# v6_io_23_24_25_26.net
KiCad netlist of a schematic drawn in Altium Designer
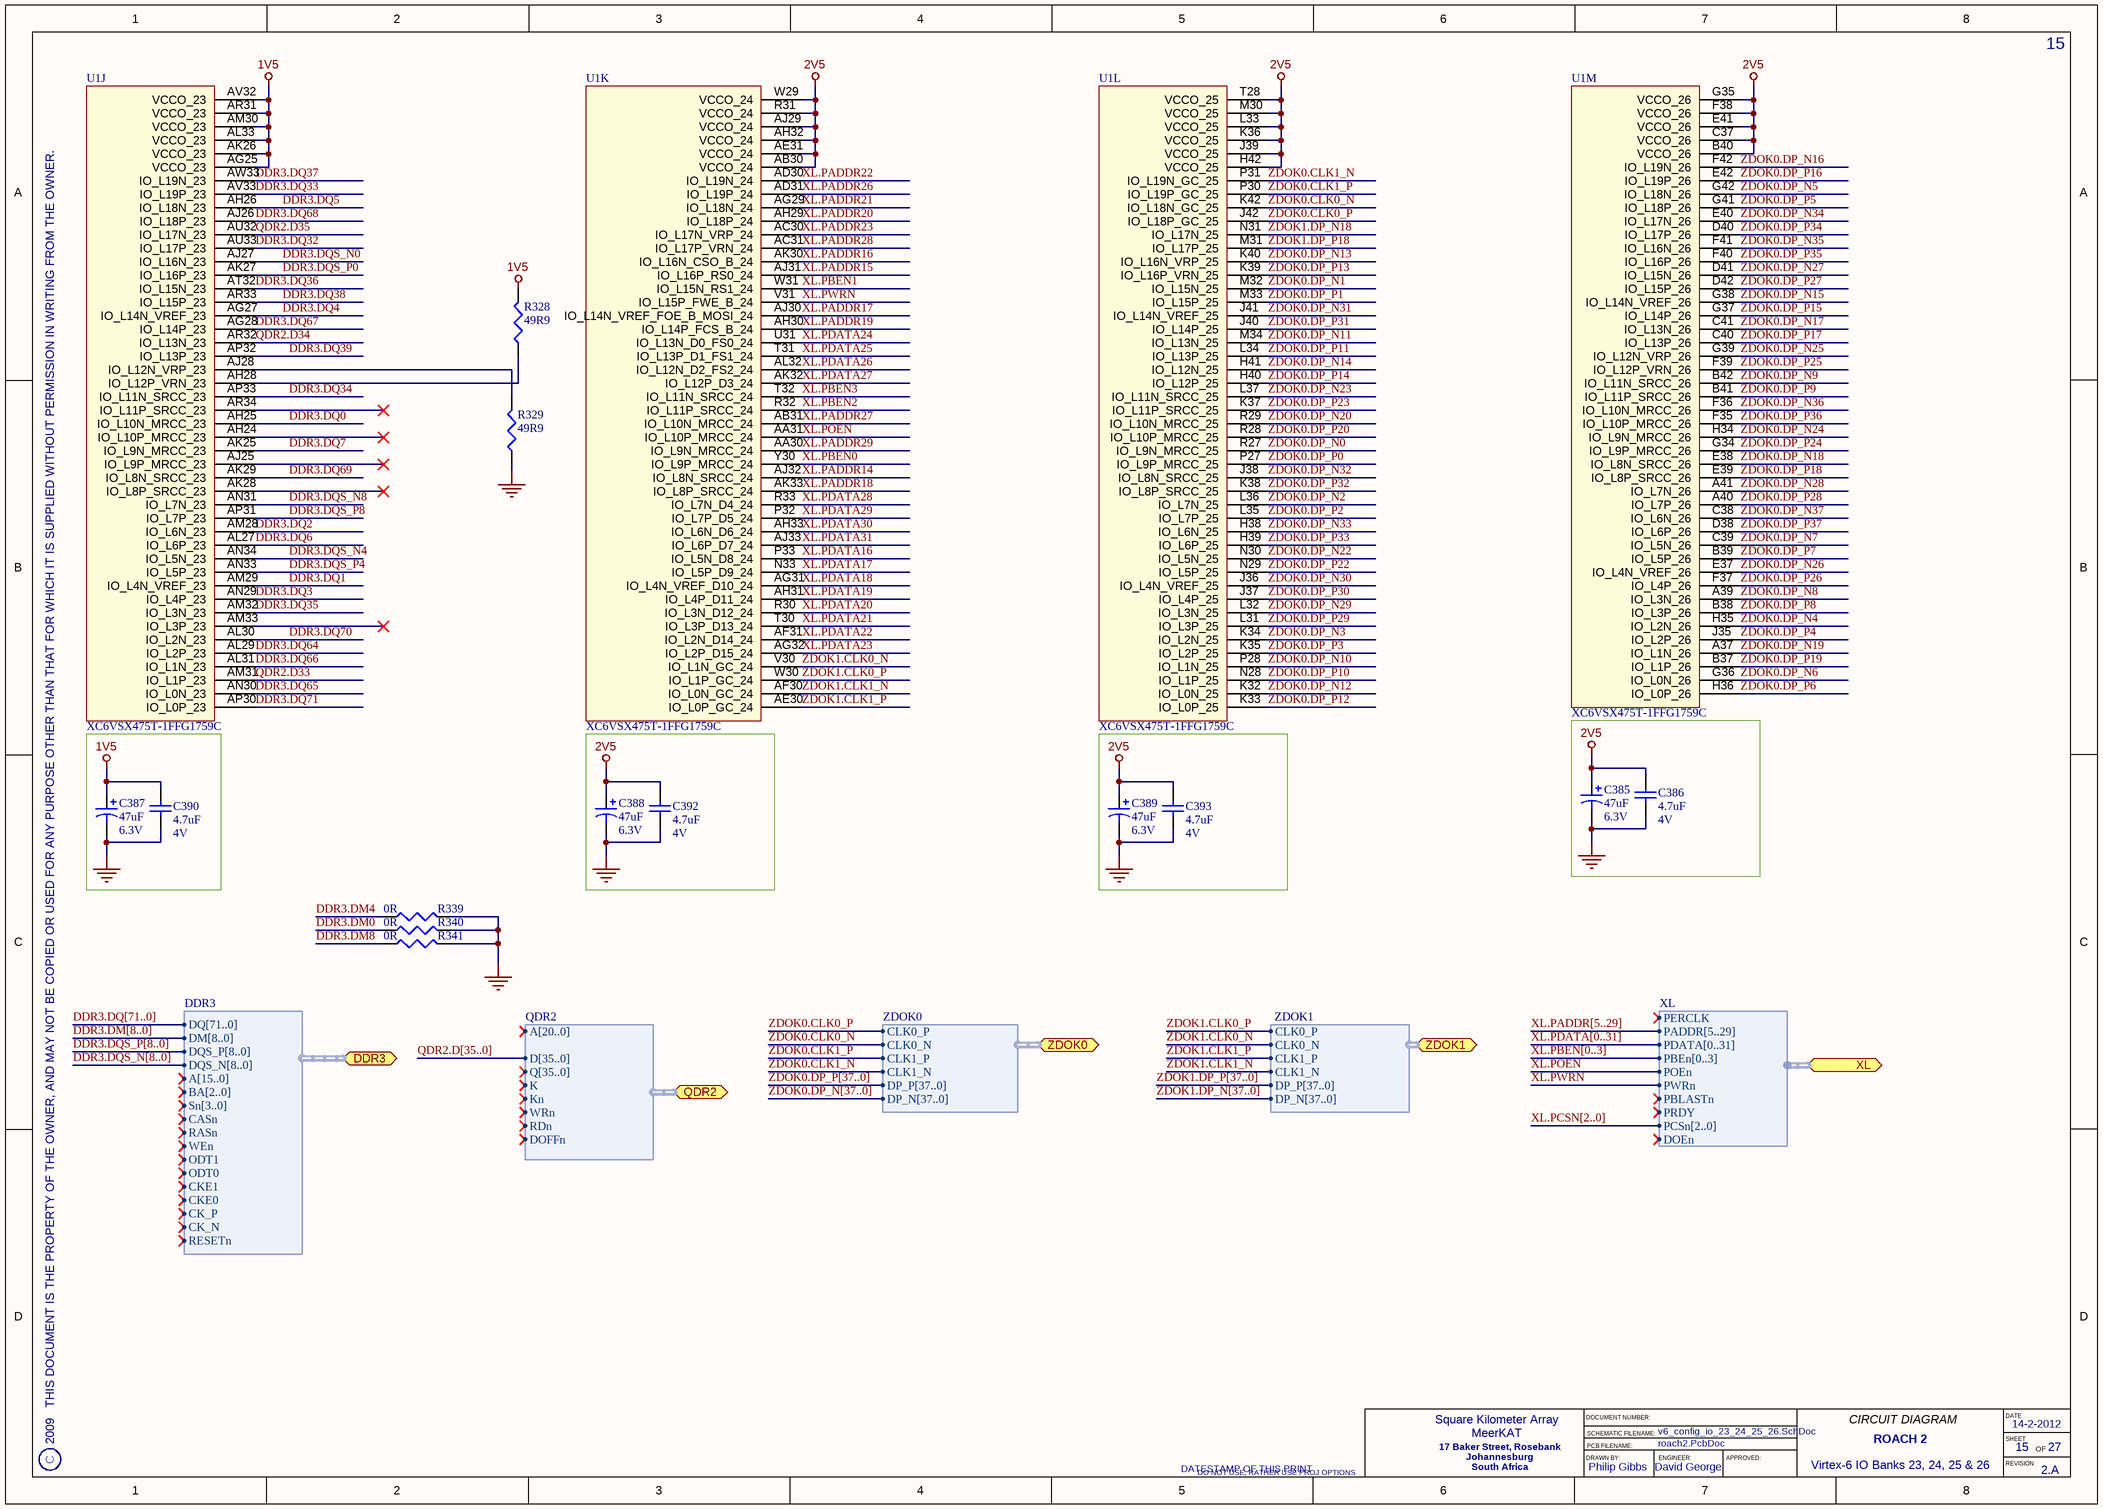
[diagram p0: v6_io_23_24_25_26.SchDoc]

(export (version "E")
  (design (tool "Eeschema 10.0.6"))
  (components
    (comp (ref "C385")
      (value "47uF")
      (footprint "CAPMP3528X120L")
      (description "47uF, Conductive Polymer Chip Capacitor")
      (fields
        (field (name "RATING") "6.3V")
        (field (name "MANUFACTURER") "KEMET")
        (field (name "PARTNUM") "T520T476M006ATE070")
      )
      (libsource (lib "altium_db") (part "CapPol"))
    )
    (comp (ref "C386")
      (value "4.7uF")
      (footprint "CAPC1005X60L")
      (description "4.7uF, Ceramic Capacitor")
      (fields
        (field (name "RATING") "4V")
        (field (name "MANUFACTURER") "MURATA")
        (field (name "PARTNUM") "AMK105BJ475MV-F")
      )
      (libsource (lib "altium_db") (part "CapStd"))
    )
    (comp (ref "C387")
      (value "47uF")
      (footprint "CAPMP3528X120L")
      (description "47uF, Conductive Polymer Chip Capacitor")
      (fields
        (field (name "RATING") "6.3V")
        (field (name "MANUFACTURER") "KEMET")
        (field (name "PARTNUM") "T520T476M006ATE070")
      )
      (libsource (lib "altium_db") (part "CapPol"))
    )
    (comp (ref "C388")
      (value "47uF")
      (footprint "CAPMP3528X120L")
      (description "47uF, Conductive Polymer Chip Capacitor")
      (fields
        (field (name "RATING") "6.3V")
        (field (name "MANUFACTURER") "KEMET")
        (field (name "PARTNUM") "T520T476M006ATE070")
      )
      (libsource (lib "altium_db") (part "CapPol"))
    )
    (comp (ref "C389")
      (value "47uF")
      (footprint "CAPMP3528X120L")
      (description "47uF, Conductive Polymer Chip Capacitor")
      (fields
        (field (name "RATING") "6.3V")
        (field (name "MANUFACTURER") "KEMET")
        (field (name "PARTNUM") "T520T476M006ATE070")
      )
      (libsource (lib "altium_db") (part "CapPol"))
    )
    (comp (ref "C390")
      (value "4.7uF")
      (footprint "CAPC1005X60L")
      (description "4.7uF, Ceramic Capacitor")
      (fields
        (field (name "RATING") "4V")
        (field (name "MANUFACTURER") "MURATA")
        (field (name "PARTNUM") "AMK105BJ475MV-F")
      )
      (libsource (lib "altium_db") (part "CapStd"))
    )
    (comp (ref "C392")
      (value "4.7uF")
      (footprint "CAPC1005X60L")
      (description "4.7uF, Ceramic Capacitor")
      (fields
        (field (name "RATING") "4V")
        (field (name "MANUFACTURER") "MURATA")
        (field (name "PARTNUM") "AMK105BJ475MV-F")
      )
      (libsource (lib "altium_db") (part "CapStd"))
    )
    (comp (ref "C393")
      (value "4.7uF")
      (footprint "CAPC1005X60L")
      (description "4.7uF, Ceramic Capacitor")
      (fields
        (field (name "RATING") "4V")
        (field (name "MANUFACTURER") "MURATA")
        (field (name "PARTNUM") "AMK105BJ475MV-F")
      )
      (libsource (lib "altium_db") (part "CapStd"))
    )
    (comp (ref "R328")
      (value "49R9")
      (footprint "RESC1005X40L")
      (description "49R9, 1.1mm x 0.5mm, Thick Film Resistor")
      (fields (field (name "MANUFACTURER") "ROYALOHM") (field (name "PARTNUM") "0402WGF499JT1E"))
      (libsource (lib "altium_db") (part "ResStd"))
    )
    (comp (ref "R329")
      (value "49R9")
      (footprint "RESC1005X40L")
      (description "49R9, 1.1mm x 0.5mm, Thick Film Resistor")
      (fields (field (name "MANUFACTURER") "ROYALOHM") (field (name "PARTNUM") "0402WGF499JT1E"))
      (libsource (lib "altium_db") (part "ResStd"))
    )
    (comp (ref "R339")
      (value "0R")
      (footprint "RESC1005X40L")
      (description "0R, 1.1mm x 0.5mm, Thick Film Resistor")
      (fields (field (name "MANUFACTURER") "ROYALOHM") (field (name "PARTNUM") "0402WG00000T1E"))
      (libsource (lib "altium_db") (part "ResStd"))
    )
    (comp (ref "R340")
      (value "0R")
      (footprint "RESC1005X40L")
      (description "0R, 1.1mm x 0.5mm, Thick Film Resistor")
      (fields (field (name "MANUFACTURER") "ROYALOHM") (field (name "PARTNUM") "0402WG00000T1E"))
      (libsource (lib "altium_db") (part "ResStd"))
    )
    (comp (ref "R341")
      (value "0R")
      (footprint "RESC1005X40L")
      (description "0R, 1.1mm x 0.5mm, Thick Film Resistor")
      (fields (field (name "MANUFACTURER") "ROYALOHM") (field (name "PARTNUM") "0402WG00000T1E"))
      (libsource (lib "altium_db") (part "ResStd"))
    )
    (comp (ref "U1")
      (value "XC6VSX475T-1FFG1759C")
      (footprint "FFG1759")
      (description "Virtex-6 475SXT 1760-pin FPGA")
      (fields (field (name "MANUFACTURER") "Xilinx"))
      (libsource (lib "altium_db") (part "XC6VSX475T-1FFG1759C"))
    )
  )
  (nets
    (net (code "171") (name "/DDR3.DM0") (class "Default")
      (node (ref "R340") (pin "1") (pinfunction "1_1") (pintype "passive"))
    )
    (net (code "172") (name "/DDR3.DM4") (class "Default")
      (node (ref "R339") (pin "1") (pinfunction "1_1") (pintype "passive"))
    )
    (net (code "173") (name "/DDR3.DM8") (class "Default")
      (node (ref "R341") (pin "1") (pinfunction "1_1") (pintype "passive"))
    )
    (net (code "175") (name "/DDR3.DQ0") (class "Default")
      (node (ref "U1") (pin "AH25") (pinfunction "IO_L10N_MRCC_23_AH25") (pintype "passive"))
    )
    (net (code "176") (name "/DDR3.DQ1") (class "Default")
      (node (ref "U1") (pin "AM29") (pinfunction "IO_L4N_VREF_23_AM29") (pintype "passive"))
    )
    (net (code "177") (name "/DDR3.DQ2") (class "Default")
      (node (ref "U1") (pin "AM28") (pinfunction "IO_L6N_23_AM28") (pintype "passive"))
    )
    (net (code "178") (name "/DDR3.DQ3") (class "Default")
      (node (ref "U1") (pin "AN29") (pinfunction "IO_L4P_23_AN29") (pintype "passive"))
    )
    (net (code "179") (name "/DDR3.DQ4") (class "Default")
      (node (ref "U1") (pin "AG27") (pinfunction "IO_L14N_VREF_23_AG27") (pintype "passive"))
    )
    (net (code "180") (name "/DDR3.DQ5") (class "Default")
      (node (ref "U1") (pin "AH26") (pinfunction "IO_L18N_23_AH26") (pintype "passive"))
    )
    (net (code "181") (name "/DDR3.DQ6") (class "Default")
      (node (ref "U1") (pin "AL27") (pinfunction "IO_L6P_23_AL27") (pintype "passive"))
    )
    (net (code "182") (name "/DDR3.DQ7") (class "Default")
      (node (ref "U1") (pin "AK25") (pinfunction "IO_L9N_MRCC_23_AK25") (pintype "passive"))
    )
    (net (code "183") (name "/DDR3.DQ32") (class "Default")
      (node (ref "U1") (pin "AU33") (pinfunction "IO_L17P_23_AU33") (pintype "passive"))
    )
    (net (code "184") (name "/DDR3.DQ33") (class "Default")
      (node (ref "U1") (pin "AV33") (pinfunction "IO_L19P_23_AV33") (pintype "passive"))
    )
    (net (code "185") (name "/DDR3.DQ34") (class "Default")
      (node (ref "U1") (pin "AP33") (pinfunction "IO_L11N_SRCC_23_AP33") (pintype "passive"))
    )
    (net (code "186") (name "/DDR3.DQ35") (class "Default")
      (node (ref "U1") (pin "AM32") (pinfunction "IO_L3N_23_AM32") (pintype "passive"))
    )
    (net (code "187") (name "/DDR3.DQ36") (class "Default")
      (node (ref "U1") (pin "AT32") (pinfunction "IO_L15N_23_AT32") (pintype "passive"))
    )
    (net (code "188") (name "/DDR3.DQ37") (class "Default")
      (node (ref "U1") (pin "AW33") (pinfunction "IO_L19N_23_AW33") (pintype "passive"))
    )
    (net (code "189") (name "/DDR3.DQ38") (class "Default")
      (node (ref "U1") (pin "AR33") (pinfunction "IO_L15P_23_AR33") (pintype "passive"))
    )
    (net (code "190") (name "/DDR3.DQ39") (class "Default")
      (node (ref "U1") (pin "AP32") (pinfunction "IO_L13P_23_AP32") (pintype "passive"))
    )
    (net (code "191") (name "/DDR3.DQ64") (class "Default")
      (node (ref "U1") (pin "AL29") (pinfunction "IO_L2P_23_AL29") (pintype "passive"))
    )
    (net (code "192") (name "/DDR3.DQ65") (class "Default")
      (node (ref "U1") (pin "AN30") (pinfunction "IO_L0N_23_AN30") (pintype "passive"))
    )
    (net (code "193") (name "/DDR3.DQ66") (class "Default")
      (node (ref "U1") (pin "AL31") (pinfunction "IO_L1N_23_AL31") (pintype "passive"))
    )
    (net (code "194") (name "/DDR3.DQ67") (class "Default")
      (node (ref "U1") (pin "AG28") (pinfunction "IO_L14P_23_AG28") (pintype "passive"))
    )
    (net (code "195") (name "/DDR3.DQ68") (class "Default")
      (node (ref "U1") (pin "AJ26") (pinfunction "IO_L18P_23_AJ26") (pintype "passive"))
    )
    (net (code "196") (name "/DDR3.DQ69") (class "Default")
      (node (ref "U1") (pin "AK29") (pinfunction "IO_L8N_SRCC_23_AK29") (pintype "passive"))
    )
    (net (code "197") (name "/DDR3.DQ70") (class "Default")
      (node (ref "U1") (pin "AL30") (pinfunction "IO_L2N_23_AL30") (pintype "passive"))
    )
    (net (code "198") (name "/DDR3.DQ71") (class "Default")
      (node (ref "U1") (pin "AP30") (pinfunction "IO_L0P_23_AP30") (pintype "passive"))
    )
    (net (code "199") (name "/DDR3.DQS_N0") (class "Default")
      (node (ref "U1") (pin "AJ27") (pinfunction "IO_L16N_23_AJ27") (pintype "passive"))
    )
    (net (code "200") (name "/DDR3.DQS_N4") (class "Default")
      (node (ref "U1") (pin "AN34") (pinfunction "IO_L5N_23_AN34") (pintype "passive"))
    )
    (net (code "201") (name "/DDR3.DQS_N8") (class "Default")
      (node (ref "U1") (pin "AN31") (pinfunction "IO_L7N_23_AN31") (pintype "passive"))
    )
    (net (code "203") (name "/DDR3.DQS_P0") (class "Default")
      (node (ref "U1") (pin "AK27") (pinfunction "IO_L16P_23_AK27") (pintype "passive"))
    )
    (net (code "204") (name "/DDR3.DQS_P4") (class "Default")
      (node (ref "U1") (pin "AN33") (pinfunction "IO_L5P_23_AN33") (pintype "passive"))
    )
    (net (code "205") (name "/DDR3.DQS_P8") (class "Default")
      (node (ref "U1") (pin "AP31") (pinfunction "IO_L7P_23_AP31") (pintype "passive"))
    )
    (net (code "208") (name "/QDR2.D33") (class "Default")
      (node (ref "U1") (pin "AM31") (pinfunction "IO_L1P_23_AM31") (pintype "passive"))
    )
    (net (code "209") (name "/QDR2.D34") (class "Default")
      (node (ref "U1") (pin "AR32") (pinfunction "IO_L13N_23_AR32") (pintype "passive"))
    )
    (net (code "210") (name "/QDR2.D35") (class "Default")
      (node (ref "U1") (pin "AU32") (pinfunction "IO_L17N_23_AU32") (pintype "passive"))
    )
    (net (code "212") (name "/XL.PADDR14") (class "Default")
      (node (ref "U1") (pin "AJ32") (pinfunction "IO_L8N_SRCC_24_AJ32") (pintype "passive"))
    )
    (net (code "213") (name "/XL.PADDR15") (class "Default")
      (node (ref "U1") (pin "AJ31") (pinfunction "IO_L16P_RS0_24_AJ31") (pintype "passive"))
    )
    (net (code "214") (name "/XL.PADDR16") (class "Default")
      (node (ref "U1") (pin "AK30") (pinfunction "IO_L16N_CSO_B_24_AK30") (pintype "passive"))
    )
    (net (code "215") (name "/XL.PADDR17") (class "Default")
      (node (ref "U1") (pin "AJ30") (pinfunction "IO_L14N_VREF_FOE_B_MOSI_24_AJ30") (pintype "passive"))
    )
    (net (code "216") (name "/XL.PADDR18") (class "Default")
      (node (ref "U1") (pin "AK33") (pinfunction "IO_L8P_SRCC_24_AK33") (pintype "passive"))
    )
    (net (code "217") (name "/XL.PADDR19") (class "Default")
      (node (ref "U1") (pin "AH30") (pinfunction "IO_L14P_FCS_B_24_AH30") (pintype "passive"))
    )
    (net (code "218") (name "/XL.PADDR20") (class "Default")
      (node (ref "U1") (pin "AH29") (pinfunction "IO_L18P_24_AH29") (pintype "passive"))
    )
    (net (code "219") (name "/XL.PADDR21") (class "Default")
      (node (ref "U1") (pin "AG29") (pinfunction "IO_L18N_24_AG29") (pintype "passive"))
    )
    (net (code "220") (name "/XL.PADDR22") (class "Default")
      (node (ref "U1") (pin "AD30") (pinfunction "IO_L19N_24_AD30") (pintype "passive"))
    )
    (net (code "221") (name "/XL.PADDR23") (class "Default")
      (node (ref "U1") (pin "AC30") (pinfunction "IO_L17N_VRP_24_AC30") (pintype "passive"))
    )
    (net (code "222") (name "/XL.PADDR26") (class "Default")
      (node (ref "U1") (pin "AD31") (pinfunction "IO_L19P_24_AD31") (pintype "passive"))
    )
    (net (code "223") (name "/XL.PADDR27") (class "Default")
      (node (ref "U1") (pin "AB31") (pinfunction "IO_L10N_MRCC_24_AB31") (pintype "passive"))
    )
    (net (code "224") (name "/XL.PADDR28") (class "Default")
      (node (ref "U1") (pin "AC31") (pinfunction "IO_L17P_VRN_24_AC31") (pintype "passive"))
    )
    (net (code "225") (name "/XL.PADDR29") (class "Default")
      (node (ref "U1") (pin "AA30") (pinfunction "IO_L9N_MRCC_24_AA30") (pintype "passive"))
    )
    (net (code "227") (name "/XL.PBEN0") (class "Default")
      (node (ref "U1") (pin "Y30") (pinfunction "IO_L9P_MRCC_24_Y30") (pintype "passive"))
    )
    (net (code "228") (name "/XL.PBEN1") (class "Default")
      (node (ref "U1") (pin "W31") (pinfunction "IO_L15N_RS1_24_W31") (pintype "passive"))
    )
    (net (code "229") (name "/XL.PBEN2") (class "Default")
      (node (ref "U1") (pin "R32") (pinfunction "IO_L11P_SRCC_24_R32") (pintype "passive"))
    )
    (net (code "230") (name "/XL.PBEN3") (class "Default")
      (node (ref "U1") (pin "T32") (pinfunction "IO_L11N_SRCC_24_T32") (pintype "passive"))
    )
    (net (code "232") (name "/XL.PDATA16") (class "Default")
      (node (ref "U1") (pin "P33") (pinfunction "IO_L5N_D8_24_P33") (pintype "passive"))
    )
    (net (code "233") (name "/XL.PDATA17") (class "Default")
      (node (ref "U1") (pin "N33") (pinfunction "IO_L5P_D9_24_N33") (pintype "passive"))
    )
    (net (code "234") (name "/XL.PDATA18") (class "Default")
      (node (ref "U1") (pin "AG31") (pinfunction "IO_L4N_VREF_D10_24_AG31") (pintype "passive"))
    )
    (net (code "235") (name "/XL.PDATA19") (class "Default")
      (node (ref "U1") (pin "AH31") (pinfunction "IO_L4P_D11_24_AH31") (pintype "passive"))
    )
    (net (code "236") (name "/XL.PDATA20") (class "Default")
      (node (ref "U1") (pin "R30") (pinfunction "IO_L3N_D12_24_R30") (pintype "passive"))
    )
    (net (code "237") (name "/XL.PDATA21") (class "Default")
      (node (ref "U1") (pin "T30") (pinfunction "IO_L3P_D13_24_T30") (pintype "passive"))
    )
    (net (code "238") (name "/XL.PDATA22") (class "Default")
      (node (ref "U1") (pin "AF31") (pinfunction "IO_L2N_D14_24_AF31") (pintype "passive"))
    )
    (net (code "239") (name "/XL.PDATA23") (class "Default")
      (node (ref "U1") (pin "AG32") (pinfunction "IO_L2P_D15_24_AG32") (pintype "passive"))
    )
    (net (code "240") (name "/XL.PDATA24") (class "Default")
      (node (ref "U1") (pin "U31") (pinfunction "IO_L13N_D0_FS0_24_U31") (pintype "passive"))
    )
    (net (code "241") (name "/XL.PDATA25") (class "Default")
      (node (ref "U1") (pin "T31") (pinfunction "IO_L13P_D1_FS1_24_T31") (pintype "passive"))
    )
    (net (code "242") (name "/XL.PDATA26") (class "Default")
      (node (ref "U1") (pin "AL32") (pinfunction "IO_L12N_D2_FS2_24_AL32") (pintype "passive"))
    )
    (net (code "243") (name "/XL.PDATA27") (class "Default")
      (node (ref "U1") (pin "AK32") (pinfunction "IO_L12P_D3_24_AK32") (pintype "passive"))
    )
    (net (code "244") (name "/XL.PDATA28") (class "Default")
      (node (ref "U1") (pin "R33") (pinfunction "IO_L7N_D4_24_R33") (pintype "passive"))
    )
    (net (code "245") (name "/XL.PDATA29") (class "Default")
      (node (ref "U1") (pin "P32") (pinfunction "IO_L7P_D5_24_P32") (pintype "passive"))
    )
    (net (code "246") (name "/XL.PDATA30") (class "Default")
      (node (ref "U1") (pin "AH33") (pinfunction "IO_L6N_D6_24_AH33") (pintype "passive"))
    )
    (net (code "247") (name "/XL.PDATA31") (class "Default")
      (node (ref "U1") (pin "AJ33") (pinfunction "IO_L6P_D7_24_AJ33") (pintype "passive"))
    )
    (net (code "249") (name "/XL.POEN") (class "Default")
      (node (ref "U1") (pin "AA31") (pinfunction "IO_L10P_MRCC_24_AA31") (pintype "passive"))
    )
    (net (code "250") (name "/XL.PWRN") (class "Default")
      (node (ref "U1") (pin "V31") (pinfunction "IO_L15P_FWE_B_24_V31") (pintype "passive"))
    )
    (net (code "252") (name "/ZDOK0.CLK0_N") (class "Default")
      (node (ref "U1") (pin "K42") (pinfunction "IO_L18N_GC_25_K42") (pintype "passive"))
    )
    (net (code "253") (name "/ZDOK0.CLK0_P") (class "Default")
      (node (ref "U1") (pin "J42") (pinfunction "IO_L18P_GC_25_J42") (pintype "passive"))
    )
    (net (code "254") (name "/ZDOK0.CLK1_N") (class "Default")
      (node (ref "U1") (pin "P31") (pinfunction "IO_L19N_GC_25_P31") (pintype "passive"))
    )
    (net (code "255") (name "/ZDOK0.CLK1_P") (class "Default")
      (node (ref "U1") (pin "P30") (pinfunction "IO_L19P_GC_25_P30") (pintype "passive"))
    )
    (net (code "256") (name "/ZDOK0.DP_N0") (class "Default")
      (node (ref "U1") (pin "R27") (pinfunction "IO_L9N_MRCC_25_R27") (pintype "passive"))
    )
    (net (code "257") (name "/ZDOK0.DP_N1") (class "Default")
      (node (ref "U1") (pin "M32") (pinfunction "IO_L15N_25_M32") (pintype "passive"))
    )
    (net (code "258") (name "/ZDOK0.DP_N2") (class "Default")
      (node (ref "U1") (pin "L36") (pinfunction "IO_L7N_25_L36") (pintype "passive"))
    )
    (net (code "259") (name "/ZDOK0.DP_N3") (class "Default")
      (node (ref "U1") (pin "K34") (pinfunction "IO_L2N_25_K34") (pintype "passive"))
    )
    (net (code "260") (name "/ZDOK0.DP_N4") (class "Default")
      (node (ref "U1") (pin "H35") (pinfunction "IO_L2N_26_H35") (pintype "passive"))
    )
    (net (code "261") (name "/ZDOK0.DP_N5") (class "Default")
      (node (ref "U1") (pin "G42") (pinfunction "IO_L18N_26_G42") (pintype "passive"))
    )
    (net (code "262") (name "/ZDOK0.DP_N6") (class "Default")
      (node (ref "U1") (pin "G36") (pinfunction "IO_L0N_26_G36") (pintype "passive"))
    )
    (net (code "263") (name "/ZDOK0.DP_N7") (class "Default")
      (node (ref "U1") (pin "C39") (pinfunction "IO_L5N_26_C39") (pintype "passive"))
    )
    (net (code "264") (name "/ZDOK0.DP_N8") (class "Default")
      (node (ref "U1") (pin "A39") (pinfunction "IO_L3N_26_A39") (pintype "passive"))
    )
    (net (code "265") (name "/ZDOK0.DP_N9") (class "Default")
      (node (ref "U1") (pin "B42") (pinfunction "IO_L11N_SRCC_26_B42") (pintype "passive"))
    )
    (net (code "266") (name "/ZDOK0.DP_N10") (class "Default")
      (node (ref "U1") (pin "P28") (pinfunction "IO_L1N_25_P28") (pintype "passive"))
    )
    (net (code "267") (name "/ZDOK0.DP_N11") (class "Default")
      (node (ref "U1") (pin "M34") (pinfunction "IO_L13N_25_M34") (pintype "passive"))
    )
    (net (code "268") (name "/ZDOK0.DP_N12") (class "Default")
      (node (ref "U1") (pin "K32") (pinfunction "IO_L0N_25_K32") (pintype "passive"))
    )
    (net (code "269") (name "/ZDOK0.DP_N13") (class "Default")
      (node (ref "U1") (pin "K40") (pinfunction "IO_L16N_VRP_25_K40") (pintype "passive"))
    )
    (net (code "270") (name "/ZDOK0.DP_N14") (class "Default")
      (node (ref "U1") (pin "H41") (pinfunction "IO_L12N_25_H41") (pintype "passive"))
    )
    (net (code "271") (name "/ZDOK0.DP_N15") (class "Default")
      (node (ref "U1") (pin "G38") (pinfunction "IO_L14N_VREF_26_G38") (pintype "passive"))
    )
    (net (code "272") (name "/ZDOK0.DP_N16") (class "Default")
      (node (ref "U1") (pin "F42") (pinfunction "IO_L19N_26_F42") (pintype "passive"))
    )
    (net (code "273") (name "/ZDOK0.DP_N17") (class "Default")
      (node (ref "U1") (pin "C41") (pinfunction "IO_L13N_26_C41") (pintype "passive"))
    )
    (net (code "274") (name "/ZDOK0.DP_N18") (class "Default")
      (node (ref "U1") (pin "E38") (pinfunction "IO_L8N_SRCC_26_E38") (pintype "passive"))
    )
    (net (code "275") (name "/ZDOK0.DP_N19") (class "Default")
      (node (ref "U1") (pin "A37") (pinfunction "IO_L1N_26_A37") (pintype "passive"))
    )
    (net (code "276") (name "/ZDOK0.DP_N20") (class "Default")
      (node (ref "U1") (pin "R29") (pinfunction "IO_L10N_MRCC_25_R29") (pintype "passive"))
    )
    (net (code "277") (name "/ZDOK0.DP_N22") (class "Default")
      (node (ref "U1") (pin "N30") (pinfunction "IO_L5N_25_N30") (pintype "passive"))
    )
    (net (code "278") (name "/ZDOK0.DP_N23") (class "Default")
      (node (ref "U1") (pin "L37") (pinfunction "IO_L11N_SRCC_25_L37") (pintype "passive"))
    )
    (net (code "279") (name "/ZDOK0.DP_N24") (class "Default")
      (node (ref "U1") (pin "H34") (pinfunction "IO_L9N_MRCC_26_H34") (pintype "passive"))
    )
    (net (code "280") (name "/ZDOK0.DP_N25") (class "Default")
      (node (ref "U1") (pin "G39") (pinfunction "IO_L12N_VRP_26_G39") (pintype "passive"))
    )
    (net (code "281") (name "/ZDOK0.DP_N26") (class "Default")
      (node (ref "U1") (pin "E37") (pinfunction "IO_L4N_VREF_26_E37") (pintype "passive"))
    )
    (net (code "282") (name "/ZDOK0.DP_N27") (class "Default")
      (node (ref "U1") (pin "D41") (pinfunction "IO_L15N_26_D41") (pintype "passive"))
    )
    (net (code "283") (name "/ZDOK0.DP_N28") (class "Default")
      (node (ref "U1") (pin "A41") (pinfunction "IO_L7N_26_A41") (pintype "passive"))
    )
    (net (code "284") (name "/ZDOK0.DP_N29") (class "Default")
      (node (ref "U1") (pin "L32") (pinfunction "IO_L3N_25_L32") (pintype "passive"))
    )
    (net (code "285") (name "/ZDOK0.DP_N30") (class "Default")
      (node (ref "U1") (pin "J36") (pinfunction "IO_L4N_VREF_25_J36") (pintype "passive"))
    )
    (net (code "286") (name "/ZDOK0.DP_N31") (class "Default")
      (node (ref "U1") (pin "J41") (pinfunction "IO_L14N_VREF_25_J41") (pintype "passive"))
    )
    (net (code "287") (name "/ZDOK0.DP_N32") (class "Default")
      (node (ref "U1") (pin "J38") (pinfunction "IO_L8N_SRCC_25_J38") (pintype "passive"))
    )
    (net (code "288") (name "/ZDOK0.DP_N33") (class "Default")
      (node (ref "U1") (pin "H38") (pinfunction "IO_L6N_25_H38") (pintype "passive"))
    )
    (net (code "289") (name "/ZDOK0.DP_N34") (class "Default")
      (node (ref "U1") (pin "E40") (pinfunction "IO_L17N_26_E40") (pintype "passive"))
    )
    (net (code "290") (name "/ZDOK0.DP_N35") (class "Default")
      (node (ref "U1") (pin "F41") (pinfunction "IO_L16N_26_F41") (pintype "passive"))
    )
    (net (code "291") (name "/ZDOK0.DP_N36") (class "Default")
      (node (ref "U1") (pin "F36") (pinfunction "IO_L10N_MRCC_26_F36") (pintype "passive"))
    )
    (net (code "292") (name "/ZDOK0.DP_N37") (class "Default")
      (node (ref "U1") (pin "C38") (pinfunction "IO_L6N_26_C38") (pintype "passive"))
    )
    (net (code "294") (name "/ZDOK0.DP_P0") (class "Default")
      (node (ref "U1") (pin "P27") (pinfunction "IO_L9P_MRCC_25_P27") (pintype "passive"))
    )
    (net (code "295") (name "/ZDOK0.DP_P1") (class "Default")
      (node (ref "U1") (pin "M33") (pinfunction "IO_L15P_25_M33") (pintype "passive"))
    )
    (net (code "296") (name "/ZDOK0.DP_P2") (class "Default")
      (node (ref "U1") (pin "L35") (pinfunction "IO_L7P_25_L35") (pintype "passive"))
    )
    (net (code "297") (name "/ZDOK0.DP_P3") (class "Default")
      (node (ref "U1") (pin "K35") (pinfunction "IO_L2P_25_K35") (pintype "passive"))
    )
    (net (code "298") (name "/ZDOK0.DP_P4") (class "Default")
      (node (ref "U1") (pin "J35") (pinfunction "IO_L2P_26_J35") (pintype "passive"))
    )
    (net (code "299") (name "/ZDOK0.DP_P5") (class "Default")
      (node (ref "U1") (pin "G41") (pinfunction "IO_L18P_26_G41") (pintype "passive"))
    )
    (net (code "300") (name "/ZDOK0.DP_P6") (class "Default")
      (node (ref "U1") (pin "H36") (pinfunction "IO_L0P_26_H36") (pintype "passive"))
    )
    (net (code "301") (name "/ZDOK0.DP_P7") (class "Default")
      (node (ref "U1") (pin "B39") (pinfunction "IO_L5P_26_B39") (pintype "passive"))
    )
    (net (code "302") (name "/ZDOK0.DP_P8") (class "Default")
      (node (ref "U1") (pin "B38") (pinfunction "IO_L3P_26_B38") (pintype "passive"))
    )
    (net (code "303") (name "/ZDOK0.DP_P9") (class "Default")
      (node (ref "U1") (pin "B41") (pinfunction "IO_L11P_SRCC_26_B41") (pintype "passive"))
    )
    (net (code "304") (name "/ZDOK0.DP_P10") (class "Default")
      (node (ref "U1") (pin "N28") (pinfunction "IO_L1P_25_N28") (pintype "passive"))
    )
    (net (code "305") (name "/ZDOK0.DP_P11") (class "Default")
      (node (ref "U1") (pin "L34") (pinfunction "IO_L13P_25_L34") (pintype "passive"))
    )
    (net (code "306") (name "/ZDOK0.DP_P12") (class "Default")
      (node (ref "U1") (pin "K33") (pinfunction "IO_L0P_25_K33") (pintype "passive"))
    )
    (net (code "307") (name "/ZDOK0.DP_P13") (class "Default")
      (node (ref "U1") (pin "K39") (pinfunction "IO_L16P_VRN_25_K39") (pintype "passive"))
    )
    (net (code "308") (name "/ZDOK0.DP_P14") (class "Default")
      (node (ref "U1") (pin "H40") (pinfunction "IO_L12P_25_H40") (pintype "passive"))
    )
    (net (code "309") (name "/ZDOK0.DP_P15") (class "Default")
      (node (ref "U1") (pin "G37") (pinfunction "IO_L14P_26_G37") (pintype "passive"))
    )
    (net (code "310") (name "/ZDOK0.DP_P16") (class "Default")
      (node (ref "U1") (pin "E42") (pinfunction "IO_L19P_26_E42") (pintype "passive"))
    )
    (net (code "311") (name "/ZDOK0.DP_P17") (class "Default")
      (node (ref "U1") (pin "C40") (pinfunction "IO_L13P_26_C40") (pintype "passive"))
    )
    (net (code "312") (name "/ZDOK0.DP_P18") (class "Default")
      (node (ref "U1") (pin "E39") (pinfunction "IO_L8P_SRCC_26_E39") (pintype "passive"))
    )
    (net (code "313") (name "/ZDOK0.DP_P19") (class "Default")
      (node (ref "U1") (pin "B37") (pinfunction "IO_L1P_26_B37") (pintype "passive"))
    )
    (net (code "314") (name "/ZDOK0.DP_P20") (class "Default")
      (node (ref "U1") (pin "R28") (pinfunction "IO_L10P_MRCC_25_R28") (pintype "passive"))
    )
    (net (code "315") (name "/ZDOK0.DP_P22") (class "Default")
      (node (ref "U1") (pin "N29") (pinfunction "IO_L5P_25_N29") (pintype "passive"))
    )
    (net (code "316") (name "/ZDOK0.DP_P23") (class "Default")
      (node (ref "U1") (pin "K37") (pinfunction "IO_L11P_SRCC_25_K37") (pintype "passive"))
    )
    (net (code "317") (name "/ZDOK0.DP_P24") (class "Default")
      (node (ref "U1") (pin "G34") (pinfunction "IO_L9P_MRCC_26_G34") (pintype "passive"))
    )
    (net (code "318") (name "/ZDOK0.DP_P25") (class "Default")
      (node (ref "U1") (pin "F39") (pinfunction "IO_L12P_VRN_26_F39") (pintype "passive"))
    )
    (net (code "319") (name "/ZDOK0.DP_P26") (class "Default")
      (node (ref "U1") (pin "F37") (pinfunction "IO_L4P_26_F37") (pintype "passive"))
    )
    (net (code "320") (name "/ZDOK0.DP_P27") (class "Default")
      (node (ref "U1") (pin "D42") (pinfunction "IO_L15P_26_D42") (pintype "passive"))
    )
    (net (code "321") (name "/ZDOK0.DP_P28") (class "Default")
      (node (ref "U1") (pin "A40") (pinfunction "IO_L7P_26_A40") (pintype "passive"))
    )
    (net (code "322") (name "/ZDOK0.DP_P29") (class "Default")
      (node (ref "U1") (pin "L31") (pinfunction "IO_L3P_25_L31") (pintype "passive"))
    )
    (net (code "323") (name "/ZDOK0.DP_P30") (class "Default")
      (node (ref "U1") (pin "J37") (pinfunction "IO_L4P_25_J37") (pintype "passive"))
    )
    (net (code "324") (name "/ZDOK0.DP_P31") (class "Default")
      (node (ref "U1") (pin "J40") (pinfunction "IO_L14P_25_J40") (pintype "passive"))
    )
    (net (code "325") (name "/ZDOK0.DP_P32") (class "Default")
      (node (ref "U1") (pin "K38") (pinfunction "IO_L8P_SRCC_25_K38") (pintype "passive"))
    )
    (net (code "326") (name "/ZDOK0.DP_P33") (class "Default")
      (node (ref "U1") (pin "H39") (pinfunction "IO_L6P_25_H39") (pintype "passive"))
    )
    (net (code "327") (name "/ZDOK0.DP_P34") (class "Default")
      (node (ref "U1") (pin "D40") (pinfunction "IO_L17P_26_D40") (pintype "passive"))
    )
    (net (code "328") (name "/ZDOK0.DP_P35") (class "Default")
      (node (ref "U1") (pin "F40") (pinfunction "IO_L16P_26_F40") (pintype "passive"))
    )
    (net (code "329") (name "/ZDOK0.DP_P36") (class "Default")
      (node (ref "U1") (pin "F35") (pinfunction "IO_L10P_MRCC_26_F35") (pintype "passive"))
    )
    (net (code "330") (name "/ZDOK0.DP_P37") (class "Default")
      (node (ref "U1") (pin "D38") (pinfunction "IO_L6P_26_D38") (pintype "passive"))
    )
    (net (code "332") (name "/ZDOK1.CLK0_N") (class "Default")
      (node (ref "U1") (pin "V30") (pinfunction "IO_L1N_GC_24_V30") (pintype "passive"))
    )
    (net (code "333") (name "/ZDOK1.CLK0_P") (class "Default")
      (node (ref "U1") (pin "W30") (pinfunction "IO_L1P_GC_24_W30") (pintype "passive"))
    )
    (net (code "334") (name "/ZDOK1.CLK1_N") (class "Default")
      (node (ref "U1") (pin "AF30") (pinfunction "IO_L0N_GC_24_AF30") (pintype "passive"))
    )
    (net (code "335") (name "/ZDOK1.CLK1_P") (class "Default")
      (node (ref "U1") (pin "AE30") (pinfunction "IO_L0P_GC_24_AE30") (pintype "passive"))
    )
    (net (code "336") (name "/ZDOK1.DP_N18") (class "Default")
      (node (ref "U1") (pin "N31") (pinfunction "IO_L17N_25_N31") (pintype "passive"))
    )
    (net (code "337") (name "/ZDOK1.DP_P18") (class "Default")
      (node (ref "U1") (pin "M31") (pinfunction "IO_L17P_25_M31") (pintype "passive"))
    )
    (net (code "344") (name "1V5") (class "Default")
      (node (ref "C387") (pin "1") (pinfunction "1_1") (pintype "passive"))
      (node (ref "C390") (pin "2") (pinfunction "2_2") (pintype "passive"))
      (node (ref "R328") (pin "2") (pinfunction "2_2") (pintype "passive"))
      (node (ref "U1") (pin "AG25") (pinfunction "VCCO_23_AG25") (pintype "passive"))
      (node (ref "U1") (pin "AK26") (pinfunction "VCCO_23_AK26") (pintype "passive"))
      (node (ref "U1") (pin "AL33") (pinfunction "VCCO_23_AL33") (pintype "passive"))
      (node (ref "U1") (pin "AM30") (pinfunction "VCCO_23_AM30") (pintype "passive"))
      (node (ref "U1") (pin "AR31") (pinfunction "VCCO_23_AR31") (pintype "passive"))
      (node (ref "U1") (pin "AV32") (pinfunction "VCCO_23_AV32") (pintype "passive"))
    )
    (net (code "345") (name "2V5") (class "Default")
      (node (ref "C385") (pin "1") (pinfunction "1_1") (pintype "passive"))
      (node (ref "C386") (pin "2") (pinfunction "2_2") (pintype "passive"))
      (node (ref "C388") (pin "1") (pinfunction "1_1") (pintype "passive"))
      (node (ref "C389") (pin "1") (pinfunction "1_1") (pintype "passive"))
      (node (ref "C392") (pin "2") (pinfunction "2_2") (pintype "passive"))
      (node (ref "C393") (pin "2") (pinfunction "2_2") (pintype "passive"))
      (node (ref "U1") (pin "AB30") (pinfunction "VCCO_24_AB30") (pintype "passive"))
      (node (ref "U1") (pin "AE31") (pinfunction "VCCO_24_AE31") (pintype "passive"))
      (node (ref "U1") (pin "AH32") (pinfunction "VCCO_24_AH32") (pintype "passive"))
      (node (ref "U1") (pin "AJ29") (pinfunction "VCCO_24_AJ29") (pintype "passive"))
      (node (ref "U1") (pin "B40") (pinfunction "VCCO_26_B40") (pintype "passive"))
      (node (ref "U1") (pin "C37") (pinfunction "VCCO_26_C37") (pintype "passive"))
      (node (ref "U1") (pin "E41") (pinfunction "VCCO_26_E41") (pintype "passive"))
      (node (ref "U1") (pin "F38") (pinfunction "VCCO_26_F38") (pintype "passive"))
      (node (ref "U1") (pin "G35") (pinfunction "VCCO_26_G35") (pintype "passive"))
      (node (ref "U1") (pin "H42") (pinfunction "VCCO_25_H42") (pintype "passive"))
      (node (ref "U1") (pin "J39") (pinfunction "VCCO_25_J39") (pintype "passive"))
      (node (ref "U1") (pin "K36") (pinfunction "VCCO_25_K36") (pintype "passive"))
      (node (ref "U1") (pin "L33") (pinfunction "VCCO_25_L33") (pintype "passive"))
      (node (ref "U1") (pin "M30") (pinfunction "VCCO_25_M30") (pintype "passive"))
      (node (ref "U1") (pin "R31") (pinfunction "VCCO_24_R31") (pintype "passive"))
      (node (ref "U1") (pin "T28") (pinfunction "VCCO_25_T28") (pintype "passive"))
      (node (ref "U1") (pin "W29") (pinfunction "VCCO_24_W29") (pintype "passive"))
    )
    (net (code "346") (name "GND") (class "Default")
      (node (ref "C385") (pin "2") (pinfunction "2_2") (pintype "passive"))
      (node (ref "C386") (pin "1") (pinfunction "1_1") (pintype "passive"))
      (node (ref "C387") (pin "2") (pinfunction "2_2") (pintype "passive"))
      (node (ref "C388") (pin "2") (pinfunction "2_2") (pintype "passive"))
      (node (ref "C389") (pin "2") (pinfunction "2_2") (pintype "passive"))
      (node (ref "C390") (pin "1") (pinfunction "1_1") (pintype "passive"))
      (node (ref "C392") (pin "1") (pinfunction "1_1") (pintype "passive"))
      (node (ref "C393") (pin "1") (pinfunction "1_1") (pintype "passive"))
      (node (ref "R329") (pin "1") (pinfunction "1_1") (pintype "passive"))
      (node (ref "R339") (pin "2") (pinfunction "2_2") (pintype "passive"))
      (node (ref "R340") (pin "2") (pinfunction "2_2") (pintype "passive"))
      (node (ref "R341") (pin "2") (pinfunction "2_2") (pintype "passive"))
    )
    (net (code "347") (name "Net-(U1J-IO_L12N_VRP_23)") (class "Default")
      (node (ref "R329") (pin "2") (pinfunction "2_2") (pintype "passive"))
      (node (ref "U1") (pin "AJ28") (pinfunction "IO_L12N_VRP_23_AJ28") (pintype "passive"))
    )
    (net (code "348") (name "Net-(U1J-IO_L12P_VRN_23)") (class "Default")
      (node (ref "R328") (pin "1") (pinfunction "1_1") (pintype "passive"))
      (node (ref "U1") (pin "AH28") (pinfunction "IO_L12P_VRN_23_AH28") (pintype "passive"))
    )
    (net (code "349") (name "unconnected-(U1J-IO_L3P_23-PadAM33)") (class "Default")
      (node (ref "U1") (pin "AM33") (pinfunction "IO_L3P_23_AM33") (pintype "passive+no_connect"))
    )
    (net (code "350") (name "unconnected-(U1J-IO_L8P_SRCC_23-PadAK28)") (class "Default")
      (node (ref "U1") (pin "AK28") (pinfunction "IO_L8P_SRCC_23_AK28") (pintype "passive+no_connect"))
    )
    (net (code "351") (name "unconnected-(U1J-IO_L9P_MRCC_23-PadAJ25)") (class "Default")
      (node (ref "U1") (pin "AJ25") (pinfunction "IO_L9P_MRCC_23_AJ25") (pintype "passive+no_connect"))
    )
    (net (code "352") (name "unconnected-(U1J-IO_L10P_MRCC_23-PadAH24)") (class "Default")
      (node (ref "U1") (pin "AH24") (pinfunction "IO_L10P_MRCC_23_AH24") (pintype "passive+no_connect"))
    )
    (net (code "353") (name "unconnected-(U1J-IO_L11P_SRCC_23-PadAR34)") (class "Default")
      (node (ref "U1") (pin "AR34") (pinfunction "IO_L11P_SRCC_23_AR34") (pintype "passive+no_connect"))
    )
  )
)
